# led_strip_8_smd.net
KiCad netlist of a schematic drawn in EAGLE
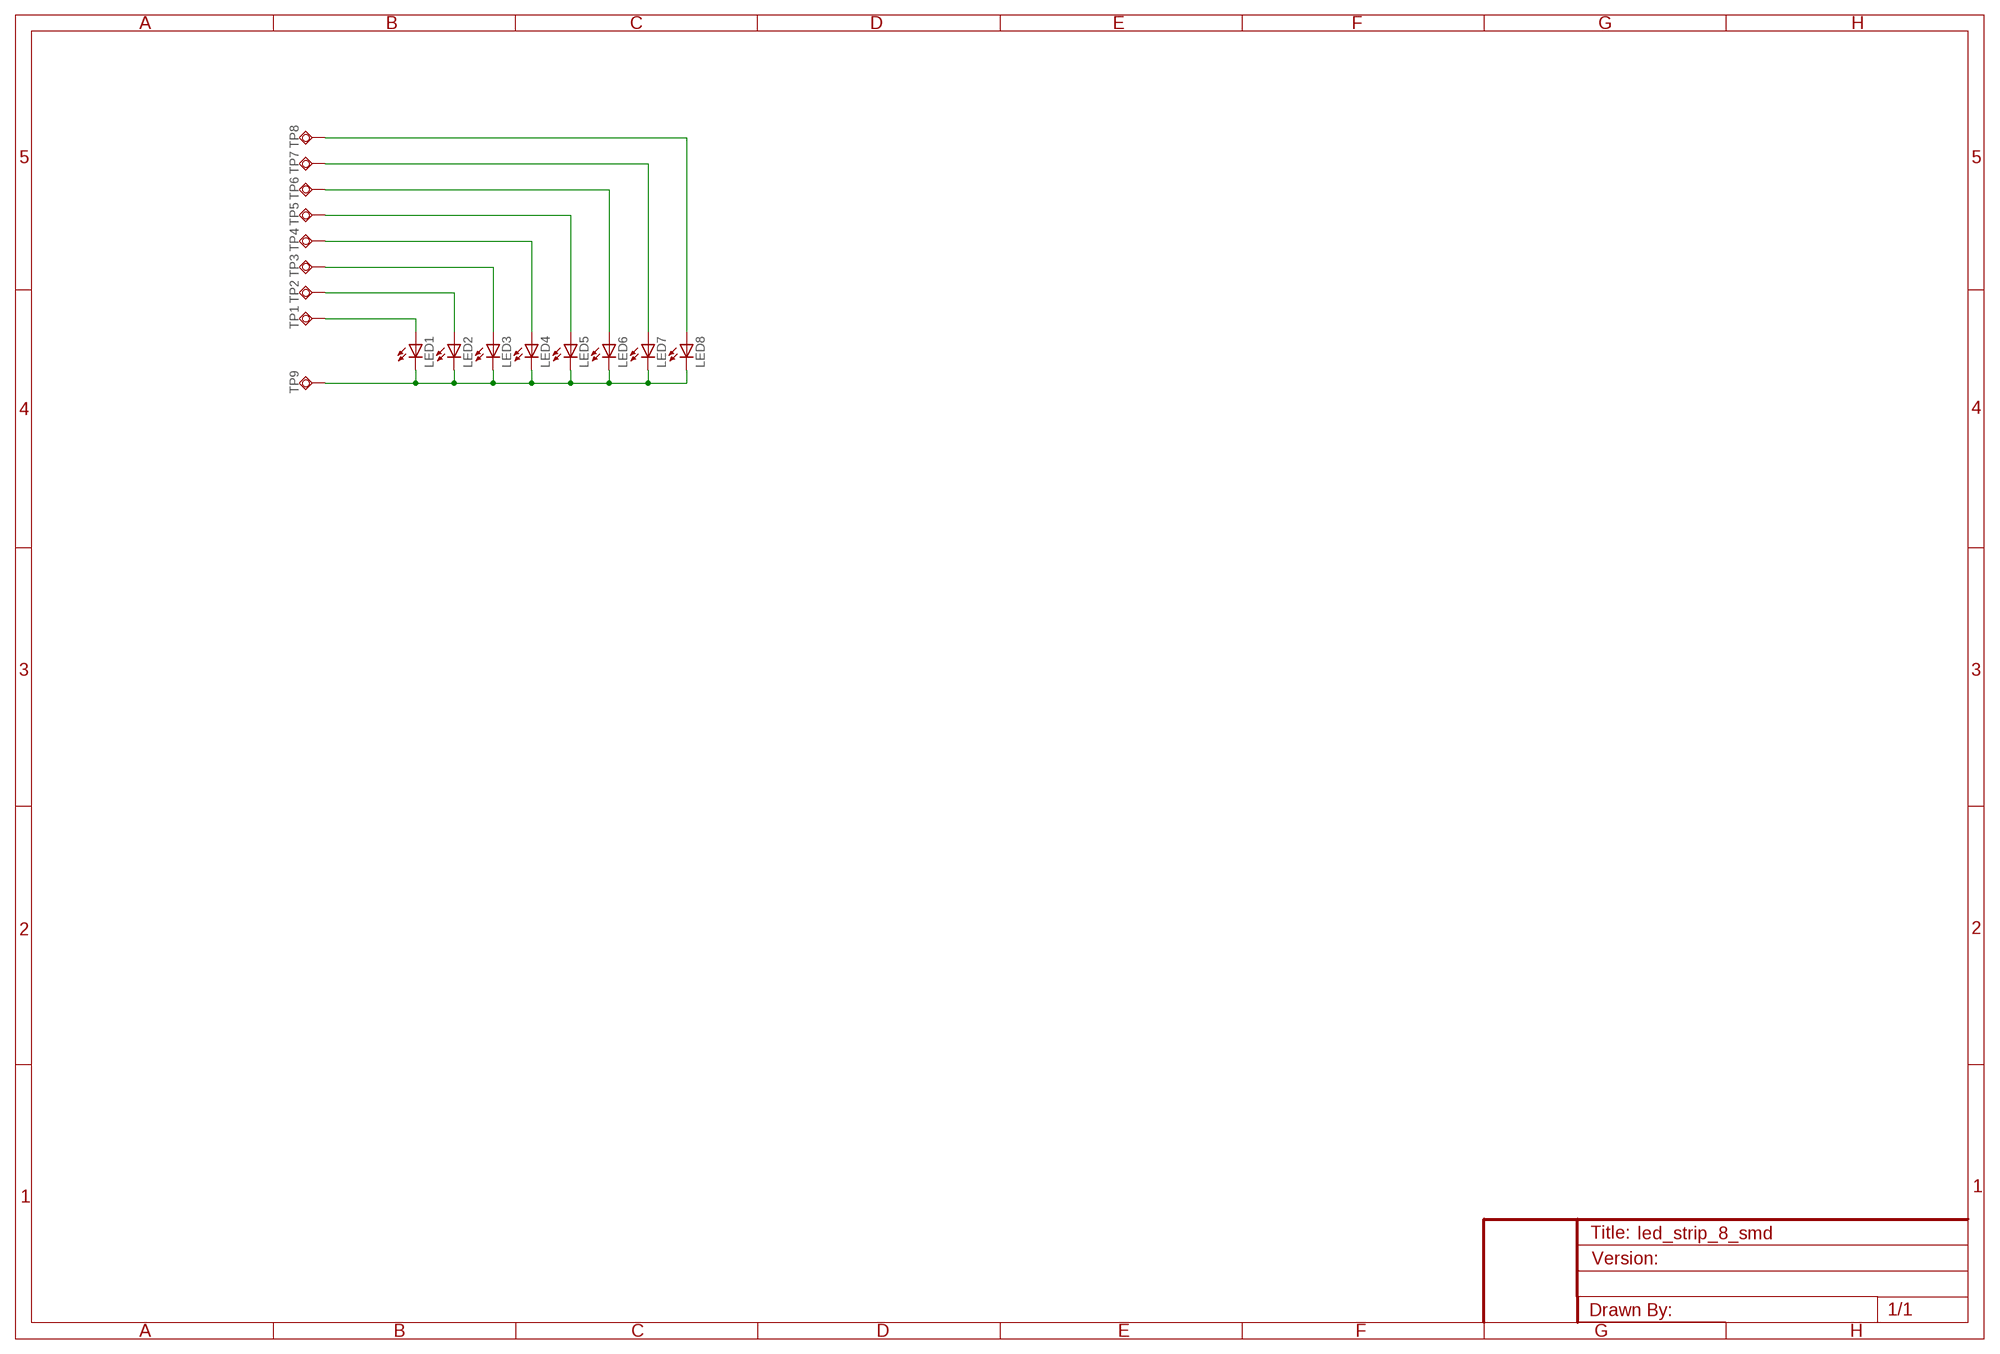
[diagram p0: schematic, sheet 1]

(export (version "E")
  (design (tool "Eeschema 10.0.6"))
  (components
    (comp (ref "LED1")
      (value "LED0805")
      (footprint "eagle-import:LED_0805")
      (libsource (lib "eagle-import") (part "LED0805"))
    )
    (comp (ref "LED2")
      (value "LED0805")
      (footprint "eagle-import:LED_0805")
      (libsource (lib "eagle-import") (part "LED0805"))
    )
    (comp (ref "LED3")
      (value "LED0805")
      (footprint "eagle-import:LED_0805")
      (libsource (lib "eagle-import") (part "LED0805"))
    )
    (comp (ref "LED4")
      (value "LED0805")
      (footprint "eagle-import:LED_0805")
      (libsource (lib "eagle-import") (part "LED0805"))
    )
    (comp (ref "LED5")
      (value "LED0805")
      (footprint "eagle-import:LED_0805")
      (libsource (lib "eagle-import") (part "LED0805"))
    )
    (comp (ref "LED6")
      (value "LED0805")
      (footprint "eagle-import:LED_0805")
      (libsource (lib "eagle-import") (part "LED0805"))
    )
    (comp (ref "LED7")
      (value "LED0805")
      (footprint "eagle-import:LED_0805")
      (libsource (lib "eagle-import") (part "LED0805"))
    )
    (comp (ref "LED8")
      (value "LED0805")
      (footprint "eagle-import:LED_0805")
      (libsource (lib "eagle-import") (part "LED0805"))
    )
    (comp (ref "TP1")
      (value "TPSQTP20SQ")
      (footprint "eagle-import:TP20SQ")
      (libsource (lib "eagle-import") (part "TPSQTP20SQ"))
    )
    (comp (ref "TP2")
      (value "TPSQTP20SQ")
      (footprint "eagle-import:TP20SQ")
      (libsource (lib "eagle-import") (part "TPSQTP20SQ"))
    )
    (comp (ref "TP3")
      (value "TPSQTP20SQ")
      (footprint "eagle-import:TP20SQ")
      (libsource (lib "eagle-import") (part "TPSQTP20SQ"))
    )
    (comp (ref "TP4")
      (value "TPSQTP20SQ")
      (footprint "eagle-import:TP20SQ")
      (libsource (lib "eagle-import") (part "TPSQTP20SQ"))
    )
    (comp (ref "TP5")
      (value "TPSQTP20SQ")
      (footprint "eagle-import:TP20SQ")
      (libsource (lib "eagle-import") (part "TPSQTP20SQ"))
    )
    (comp (ref "TP6")
      (value "TPSQTP20SQ")
      (footprint "eagle-import:TP20SQ")
      (libsource (lib "eagle-import") (part "TPSQTP20SQ"))
    )
    (comp (ref "TP7")
      (value "TPSQTP20SQ")
      (footprint "eagle-import:TP20SQ")
      (libsource (lib "eagle-import") (part "TPSQTP20SQ"))
    )
    (comp (ref "TP8")
      (value "TPSQTP20SQ")
      (footprint "eagle-import:TP20SQ")
      (libsource (lib "eagle-import") (part "TPSQTP20SQ"))
    )
    (comp (ref "TP9")
      (value "TPSQTP20SQ")
      (footprint "eagle-import:TP20SQ")
      (libsource (lib "eagle-import") (part "TPSQTP20SQ"))
    )
  )
  (nets
    (net (code "1") (name "Net-(LED1-PadA)") (class "Default")
      (node (ref "LED1") (pin "A") (pinfunction "A_A") (pintype "passive"))
      (node (ref "TP1") (pin "TP") (pinfunction "TP_TP") (pintype "input"))
    )
    (net (code "2") (name "Net-(LED1-PadC)") (class "Default")
      (node (ref "LED1") (pin "C") (pinfunction "C_C") (pintype "passive"))
      (node (ref "LED2") (pin "C") (pinfunction "C_C") (pintype "passive"))
      (node (ref "LED3") (pin "C") (pinfunction "C_C") (pintype "passive"))
      (node (ref "LED4") (pin "C") (pinfunction "C_C") (pintype "passive"))
      (node (ref "LED5") (pin "C") (pinfunction "C_C") (pintype "passive"))
      (node (ref "LED6") (pin "C") (pinfunction "C_C") (pintype "passive"))
      (node (ref "LED7") (pin "C") (pinfunction "C_C") (pintype "passive"))
      (node (ref "LED8") (pin "C") (pinfunction "C_C") (pintype "passive"))
      (node (ref "TP9") (pin "TP") (pinfunction "TP_TP") (pintype "input"))
    )
    (net (code "3") (name "Net-(LED2-PadA)") (class "Default")
      (node (ref "LED2") (pin "A") (pinfunction "A_A") (pintype "passive"))
      (node (ref "TP2") (pin "TP") (pinfunction "TP_TP") (pintype "input"))
    )
    (net (code "4") (name "Net-(LED3-PadA)") (class "Default")
      (node (ref "LED3") (pin "A") (pinfunction "A_A") (pintype "passive"))
      (node (ref "TP3") (pin "TP") (pinfunction "TP_TP") (pintype "input"))
    )
    (net (code "5") (name "Net-(LED4-PadA)") (class "Default")
      (node (ref "LED4") (pin "A") (pinfunction "A_A") (pintype "passive"))
      (node (ref "TP4") (pin "TP") (pinfunction "TP_TP") (pintype "input"))
    )
    (net (code "6") (name "Net-(LED5-PadA)") (class "Default")
      (node (ref "LED5") (pin "A") (pinfunction "A_A") (pintype "passive"))
      (node (ref "TP5") (pin "TP") (pinfunction "TP_TP") (pintype "input"))
    )
    (net (code "7") (name "Net-(LED6-PadA)") (class "Default")
      (node (ref "LED6") (pin "A") (pinfunction "A_A") (pintype "passive"))
      (node (ref "TP6") (pin "TP") (pinfunction "TP_TP") (pintype "input"))
    )
    (net (code "8") (name "Net-(LED7-PadA)") (class "Default")
      (node (ref "LED7") (pin "A") (pinfunction "A_A") (pintype "passive"))
      (node (ref "TP7") (pin "TP") (pinfunction "TP_TP") (pintype "input"))
    )
    (net (code "9") (name "Net-(LED8-PadA)") (class "Default")
      (node (ref "LED8") (pin "A") (pinfunction "A_A") (pintype "passive"))
      (node (ref "TP8") (pin "TP") (pinfunction "TP_TP") (pintype "input"))
    )
  )
)
